# Actuators.net
KiCad netlist of a schematic drawn in Altium Designer
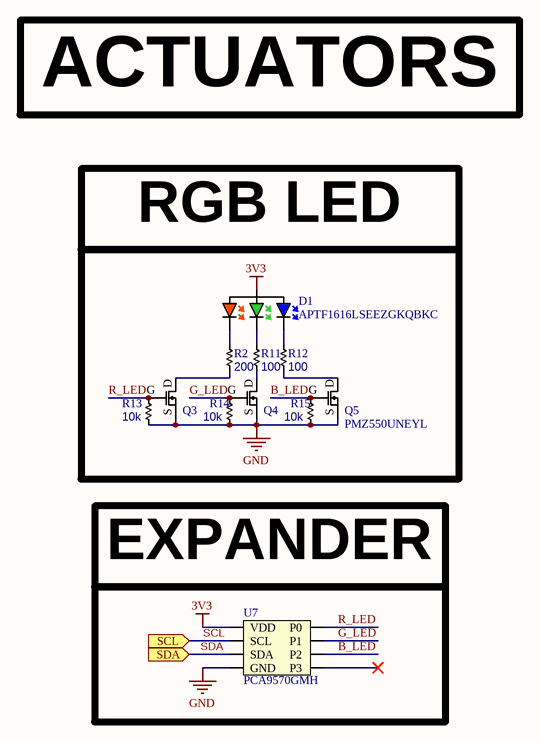
[diagram p0: Actuators.SchDoc]

(export (version "E")
  (design (tool "Eeschema 10.0.6"))
  (components
    (comp (ref "D1")
      (value "APTF1616LSEEZGKQBKC")
      (footprint "APTF1616LSEEZGKQBKC")
      (libsource (lib "smLib") (part "APTF1616LSEEZGKQBKC"))
    )
    (comp (ref "Q3")
      (value "PMZ550UNEYL")
      (footprint "PMZ550UNEYL")
      (description "PMZ550UNEYL N-Channel 30V 590mA (Ta) 310mW (Ta), 1.67W (Tc) Surface Mount DFN1006-3")
      (libsource (lib "smLib") (part "PMZ550UNEYL"))
    )
    (comp (ref "Q4")
      (value "PMZ550UNEYL")
      (footprint "PMZ550UNEYL")
      (description "PMZ550UNEYL N-Channel 30V 590mA (Ta) 310mW (Ta), 1.67W (Tc) Surface Mount DFN1006-3")
      (libsource (lib "smLib") (part "PMZ550UNEYL"))
    )
    (comp (ref "Q5")
      (value "PMZ550UNEYL")
      (footprint "PMZ550UNEYL")
      (description "PMZ550UNEYL N-Channel 30V 590mA (Ta) 310mW (Ta), 1.67W (Tc) Surface Mount DFN1006-3")
      (libsource (lib "smLib") (part "PMZ550UNEYL"))
    )
    (comp (ref "R2")
      (value "200")
      (footprint "RES_0402_HIGH")
      (description "0402 Resistor")
      (libsource (lib "smLib") (part "Resistor_0402"))
    )
    (comp (ref "R11")
      (value "100")
      (footprint "RES_0402_HIGH")
      (description "0402 Resistor")
      (libsource (lib "smLib") (part "Resistor_0402"))
    )
    (comp (ref "R12")
      (value "100")
      (footprint "RES_0402_HIGH")
      (description "0402 Resistor")
      (libsource (lib "smLib") (part "Resistor_0402"))
    )
    (comp (ref "R13")
      (value "10k")
      (footprint "RES_0402_HIGH")
      (description "0402 Resistor")
      (libsource (lib "smLib") (part "Resistor_0402"))
    )
    (comp (ref "R14")
      (value "10k")
      (footprint "RES_0402_HIGH")
      (description "0402 Resistor")
      (libsource (lib "smLib") (part "Resistor_0402"))
    )
    (comp (ref "R15")
      (value "10k")
      (footprint "RES_0402_HIGH")
      (description "0402 Resistor")
      (libsource (lib "smLib") (part "Resistor_0402"))
    )
    (comp (ref "U7")
      (value "PCA9570GMH")
      (footprint "PCA9570GMH")
      (description "PCA9570GMH I/O Expander 4 I²C, SMBus 100kHz 8-XQFN (1.6x1.6)")
      (libsource (lib "smLib") (part "PCA9570GMH"))
    )
  )
  (nets
    (net (code "1") (name "/B_LED") (class "Default")
      (node (ref "Q5") (pin "G") (pinfunction "G_G") (pintype "passive"))
      (node (ref "R15") (pin "2") (pinfunction "2_2") (pintype "passive"))
      (node (ref "U7") (pin "3") (pinfunction "P2_3") (pintype "passive"))
    )
    (net (code "2") (name "/G_LED") (class "Default")
      (node (ref "Q4") (pin "G") (pinfunction "G_G") (pintype "passive"))
      (node (ref "R14") (pin "2") (pinfunction "2_2") (pintype "passive"))
      (node (ref "U7") (pin "2") (pinfunction "P1_2") (pintype "passive"))
    )
    (net (code "3") (name "/R_LED") (class "Default")
      (node (ref "Q3") (pin "G") (pinfunction "G_G") (pintype "passive"))
      (node (ref "R13") (pin "2") (pinfunction "2_2") (pintype "passive"))
      (node (ref "U7") (pin "1") (pinfunction "P0_1") (pintype "passive"))
    )
    (net (code "4") (name "/SCL") (class "Default")
      (node (ref "U7") (pin "6") (pinfunction "SCL_6") (pintype "passive"))
    )
    (net (code "5") (name "/SDA") (class "Default")
      (node (ref "U7") (pin "7") (pinfunction "SDA_7") (pintype "passive"))
    )
    (net (code "6") (name "3V3") (class "Default")
      (node (ref "D1") (pin "1") (pinfunction "1_1") (pintype "passive"))
      (node (ref "U7") (pin "8") (pinfunction "VDD_8") (pintype "passive"))
    )
    (net (code "7") (name "GND") (class "Default")
      (node (ref "Q3") (pin "S") (pinfunction "S_S") (pintype "passive"))
      (node (ref "Q4") (pin "S") (pinfunction "S_S") (pintype "passive"))
      (node (ref "Q5") (pin "S") (pinfunction "S_S") (pintype "passive"))
      (node (ref "R13") (pin "1") (pinfunction "1_1") (pintype "passive"))
      (node (ref "R14") (pin "1") (pinfunction "1_1") (pintype "passive"))
      (node (ref "R15") (pin "1") (pinfunction "1_1") (pintype "passive"))
      (node (ref "U7") (pin "4") (pinfunction "GND_4") (pintype "passive"))
    )
    (net (code "8") (name "Net-(D1-Pad2)") (class "Default")
      (node (ref "D1") (pin "2") (pinfunction "2_2") (pintype "passive"))
      (node (ref "R2") (pin "2") (pinfunction "2_2") (pintype "passive"))
    )
    (net (code "9") (name "Net-(D1-Pad3)") (class "Default")
      (node (ref "D1") (pin "3") (pinfunction "3_3") (pintype "passive"))
      (node (ref "R11") (pin "2") (pinfunction "2_2") (pintype "passive"))
    )
    (net (code "10") (name "Net-(D1-Pad4)") (class "Default")
      (node (ref "D1") (pin "4") (pinfunction "4_4") (pintype "passive"))
      (node (ref "R12") (pin "2") (pinfunction "2_2") (pintype "passive"))
    )
    (net (code "11") (name "Net-(Q3-PadD)") (class "Default")
      (node (ref "Q3") (pin "D") (pinfunction "D_D") (pintype "passive"))
      (node (ref "R2") (pin "1") (pinfunction "1_1") (pintype "passive"))
    )
    (net (code "12") (name "Net-(Q4-PadD)") (class "Default")
      (node (ref "Q4") (pin "D") (pinfunction "D_D") (pintype "passive"))
      (node (ref "R11") (pin "1") (pinfunction "1_1") (pintype "passive"))
    )
    (net (code "13") (name "Net-(Q5-PadD)") (class "Default")
      (node (ref "Q5") (pin "D") (pinfunction "D_D") (pintype "passive"))
      (node (ref "R12") (pin "1") (pinfunction "1_1") (pintype "passive"))
    )
    (net (code "14") (name "unconnected-(U7-P3-Pad5)") (class "Default")
      (node (ref "U7") (pin "5") (pinfunction "P3_5") (pintype "passive+no_connect"))
    )
  )
)
